# plinkykeeb_choc_12Feb2022.net
KiCad netlist of a schematic drawn in EAGLE
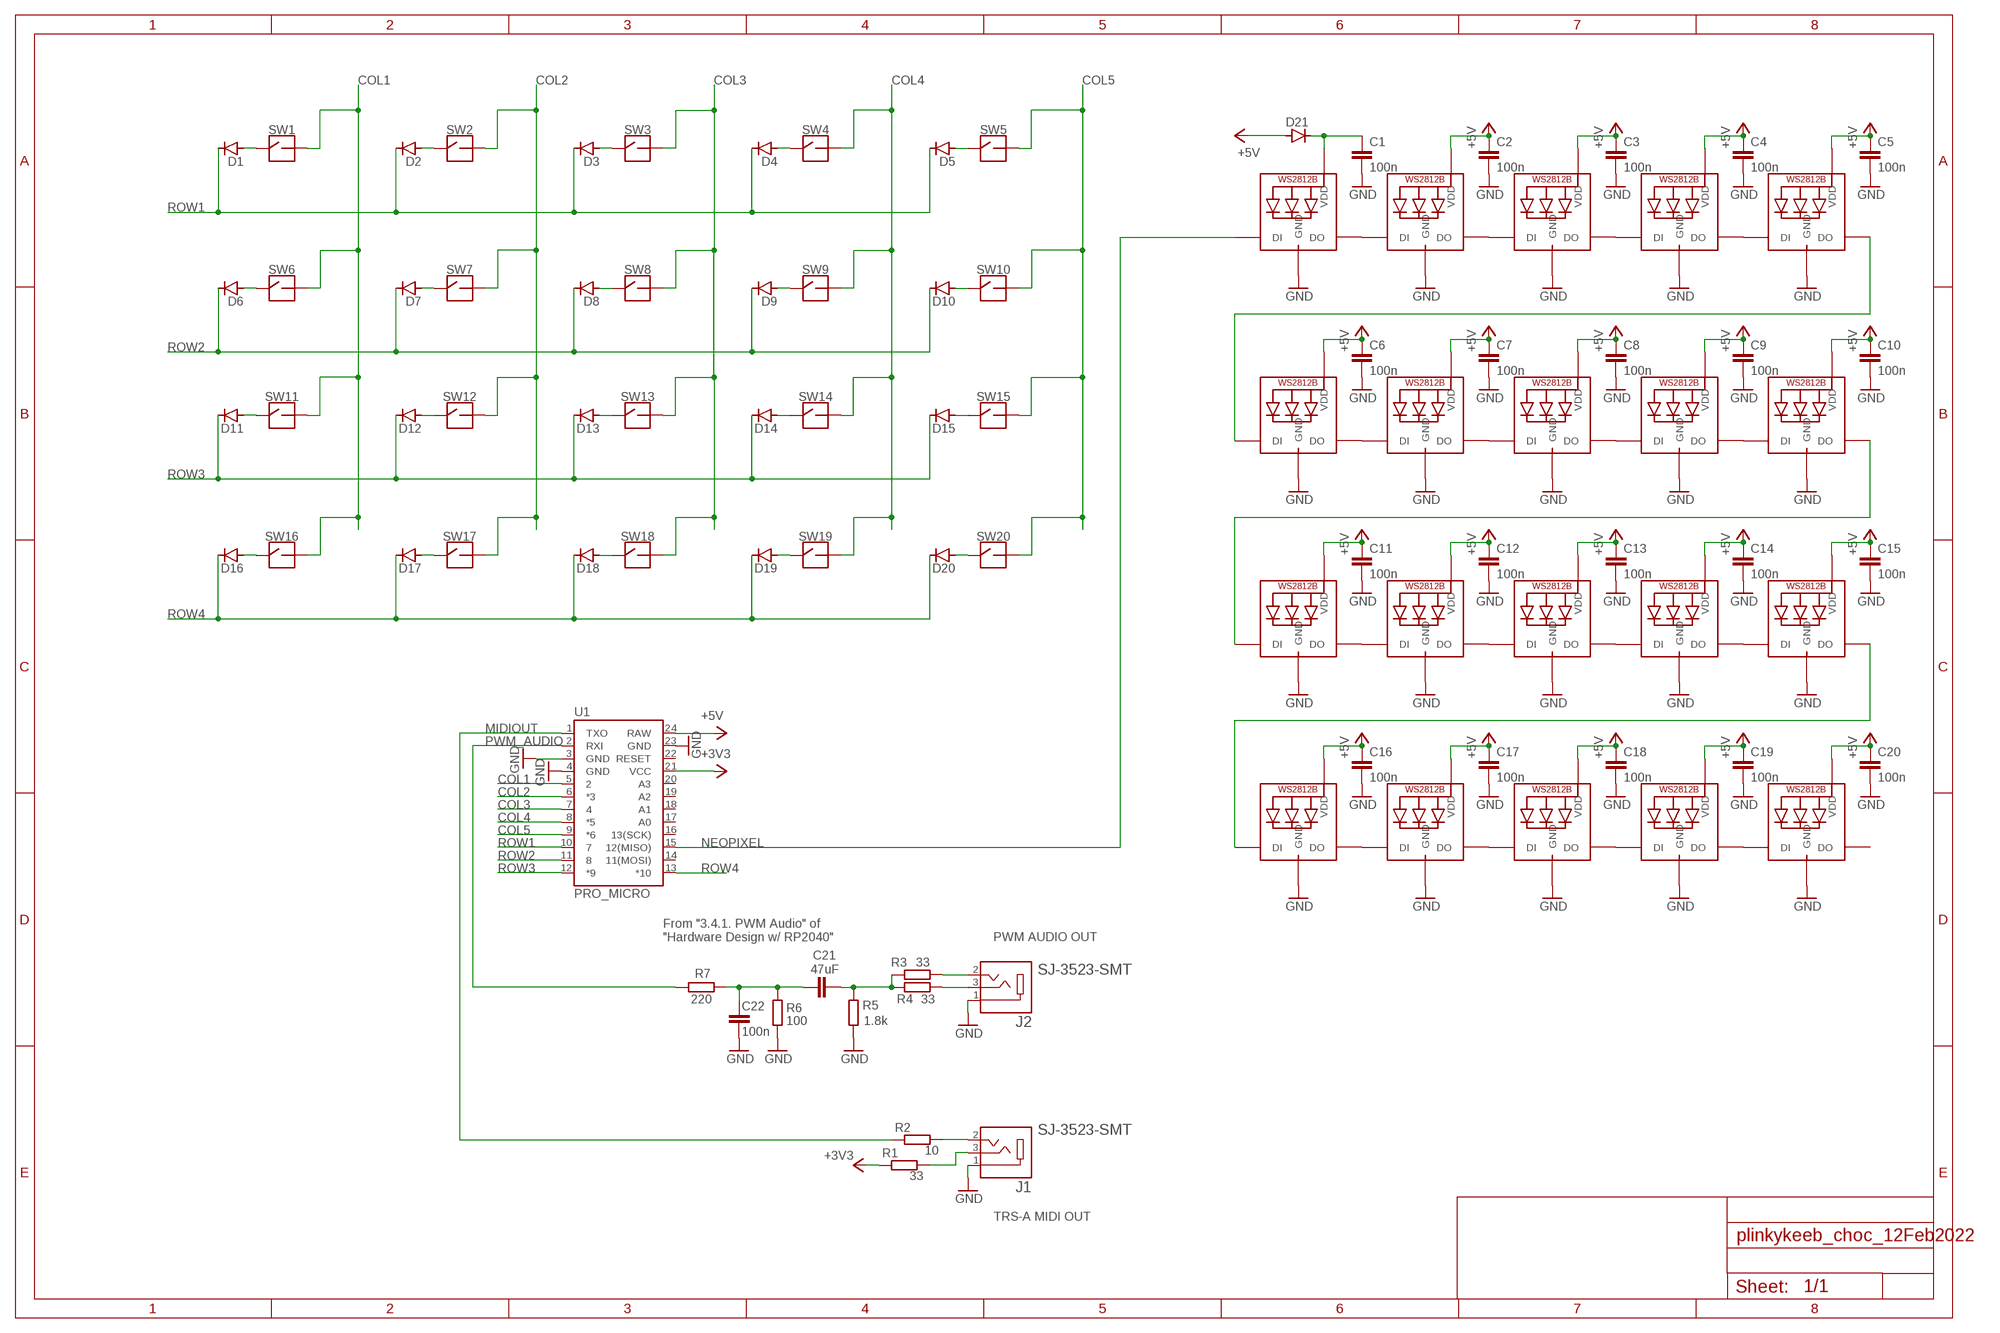
[diagram p0: schematic, sheet 1]

(export (version "E")
  (design (tool "Eeschema 10.0.6"))
  (components
    (comp (ref "C1")
      (value "100n")
      (footprint "eagle-import:C0805")
      (libsource (lib "eagle-import") (part "C-EUC0805"))
    )
    (comp (ref "C2")
      (value "100n")
      (footprint "eagle-import:C0805")
      (libsource (lib "eagle-import") (part "C-EUC0805"))
    )
    (comp (ref "C3")
      (value "100n")
      (footprint "eagle-import:C0805")
      (libsource (lib "eagle-import") (part "C-EUC0805"))
    )
    (comp (ref "C4")
      (value "100n")
      (footprint "eagle-import:C0805")
      (libsource (lib "eagle-import") (part "C-EUC0805"))
    )
    (comp (ref "C5")
      (value "100n")
      (footprint "eagle-import:C0805")
      (libsource (lib "eagle-import") (part "C-EUC0805"))
    )
    (comp (ref "C6")
      (value "100n")
      (footprint "eagle-import:C0805")
      (libsource (lib "eagle-import") (part "C-EUC0805"))
    )
    (comp (ref "C7")
      (value "100n")
      (footprint "eagle-import:C0805")
      (libsource (lib "eagle-import") (part "C-EUC0805"))
    )
    (comp (ref "C8")
      (value "100n")
      (footprint "eagle-import:C0805")
      (libsource (lib "eagle-import") (part "C-EUC0805"))
    )
    (comp (ref "C9")
      (value "100n")
      (footprint "eagle-import:C0805")
      (libsource (lib "eagle-import") (part "C-EUC0805"))
    )
    (comp (ref "C10")
      (value "100n")
      (footprint "eagle-import:C0805")
      (libsource (lib "eagle-import") (part "C-EUC0805"))
    )
    (comp (ref "C11")
      (value "100n")
      (footprint "eagle-import:C0805")
      (libsource (lib "eagle-import") (part "C-EUC0805"))
    )
    (comp (ref "C12")
      (value "100n")
      (footprint "eagle-import:C0805")
      (libsource (lib "eagle-import") (part "C-EUC0805"))
    )
    (comp (ref "C13")
      (value "100n")
      (footprint "eagle-import:C0805")
      (libsource (lib "eagle-import") (part "C-EUC0805"))
    )
    (comp (ref "C14")
      (value "100n")
      (footprint "eagle-import:C0805")
      (libsource (lib "eagle-import") (part "C-EUC0805"))
    )
    (comp (ref "C15")
      (value "100n")
      (footprint "eagle-import:C0805")
      (libsource (lib "eagle-import") (part "C-EUC0805"))
    )
    (comp (ref "C16")
      (value "100n")
      (footprint "eagle-import:C0805")
      (libsource (lib "eagle-import") (part "C-EUC0805"))
    )
    (comp (ref "C17")
      (value "100n")
      (footprint "eagle-import:C0805")
      (libsource (lib "eagle-import") (part "C-EUC0805"))
    )
    (comp (ref "C18")
      (value "100n")
      (footprint "eagle-import:C0805")
      (libsource (lib "eagle-import") (part "C-EUC0805"))
    )
    (comp (ref "C19")
      (value "100n")
      (footprint "eagle-import:C0805")
      (libsource (lib "eagle-import") (part "C-EUC0805"))
    )
    (comp (ref "C20")
      (value "100n")
      (footprint "eagle-import:C0805")
      (libsource (lib "eagle-import") (part "C-EUC0805"))
    )
    (comp (ref "C21")
      (value "47uF")
      (footprint "eagle-import:C0805")
      (libsource (lib "eagle-import") (part "C-EUC0805"))
    )
    (comp (ref "C22")
      (value "100n")
      (footprint "eagle-import:C0805")
      (libsource (lib "eagle-import") (part "C-EUC0805"))
    )
    (comp (ref "D1")
      (value "D-SOD123")
      (footprint "eagle-import:SOD123")
      (libsource (lib "eagle-import") (part "D-SOD123"))
    )
    (comp (ref "D2")
      (value "D-SOD123")
      (footprint "eagle-import:SOD123")
      (libsource (lib "eagle-import") (part "D-SOD123"))
    )
    (comp (ref "D3")
      (value "D-SOD123")
      (footprint "eagle-import:SOD123")
      (libsource (lib "eagle-import") (part "D-SOD123"))
    )
    (comp (ref "D4")
      (value "D-SOD123")
      (footprint "eagle-import:SOD123")
      (libsource (lib "eagle-import") (part "D-SOD123"))
    )
    (comp (ref "D5")
      (value "D-SOD123")
      (footprint "eagle-import:SOD123")
      (libsource (lib "eagle-import") (part "D-SOD123"))
    )
    (comp (ref "D6")
      (value "D-SOD123")
      (footprint "eagle-import:SOD123")
      (libsource (lib "eagle-import") (part "D-SOD123"))
    )
    (comp (ref "D7")
      (value "D-SOD123")
      (footprint "eagle-import:SOD123")
      (libsource (lib "eagle-import") (part "D-SOD123"))
    )
    (comp (ref "D8")
      (value "D-SOD123")
      (footprint "eagle-import:SOD123")
      (libsource (lib "eagle-import") (part "D-SOD123"))
    )
    (comp (ref "D9")
      (value "D-SOD123")
      (footprint "eagle-import:SOD123")
      (libsource (lib "eagle-import") (part "D-SOD123"))
    )
    (comp (ref "D10")
      (value "D-SOD123")
      (footprint "eagle-import:SOD123")
      (libsource (lib "eagle-import") (part "D-SOD123"))
    )
    (comp (ref "D11")
      (value "D-SOD123")
      (footprint "eagle-import:SOD123")
      (libsource (lib "eagle-import") (part "D-SOD123"))
    )
    (comp (ref "D12")
      (value "D-SOD123")
      (footprint "eagle-import:SOD123")
      (libsource (lib "eagle-import") (part "D-SOD123"))
    )
    (comp (ref "D13")
      (value "D-SOD123")
      (footprint "eagle-import:SOD123")
      (libsource (lib "eagle-import") (part "D-SOD123"))
    )
    (comp (ref "D14")
      (value "D-SOD123")
      (footprint "eagle-import:SOD123")
      (libsource (lib "eagle-import") (part "D-SOD123"))
    )
    (comp (ref "D15")
      (value "D-SOD123")
      (footprint "eagle-import:SOD123")
      (libsource (lib "eagle-import") (part "D-SOD123"))
    )
    (comp (ref "D16")
      (value "D-SOD123")
      (footprint "eagle-import:SOD123")
      (libsource (lib "eagle-import") (part "D-SOD123"))
    )
    (comp (ref "D17")
      (value "D-SOD123")
      (footprint "eagle-import:SOD123")
      (libsource (lib "eagle-import") (part "D-SOD123"))
    )
    (comp (ref "D18")
      (value "D-SOD123")
      (footprint "eagle-import:SOD123")
      (libsource (lib "eagle-import") (part "D-SOD123"))
    )
    (comp (ref "D19")
      (value "D-SOD123")
      (footprint "eagle-import:SOD123")
      (libsource (lib "eagle-import") (part "D-SOD123"))
    )
    (comp (ref "D20")
      (value "D-SOD123")
      (footprint "eagle-import:SOD123")
      (libsource (lib "eagle-import") (part "D-SOD123"))
    )
    (comp (ref "D21")
      (value "D-SOD123")
      (footprint "eagle-import:SOD123")
      (libsource (lib "eagle-import") (part "D-SOD123"))
    )
    (comp (ref "J1")
      (value "SJ-3523-SMT")
      (footprint "eagle-import:CUI_SJ-3523-SMT")
      (fields
        (field (name "DIGI-KEY_PART_NUMBER") "CP-3523SJCT-ND")
        (field (name "MF") "CUI Devices")
        (field (name "MP") "SJ-3523-SMT-TR")
      )
      (libsource (lib "eagle-import") (part "SJ-3523-SMT"))
    )
    (comp (ref "J2")
      (value "SJ-3523-SMT")
      (footprint "eagle-import:CUI_SJ-3523-SMT")
      (fields
        (field (name "DIGI-KEY_PART_NUMBER") "CP-3523SJCT-ND")
        (field (name "MF") "CUI Devices")
        (field (name "MP") "SJ-3523-SMT-TR")
      )
      (libsource (lib "eagle-import") (part "SJ-3523-SMT"))
    )
    (comp (ref "LED1")
      (value "MICROBUILDER_WS2812B_SK6812E")
      (footprint "eagle-import:MICROBUILDER_NEO3535_REVERSE")
      (libsource (lib "eagle-import") (part "MICROBUILDER_WS2812B_SK6812E"))
    )
    (comp (ref "LED2")
      (value "MICROBUILDER_WS2812B_SK6812E")
      (footprint "eagle-import:MICROBUILDER_NEO3535_REVERSE")
      (libsource (lib "eagle-import") (part "MICROBUILDER_WS2812B_SK6812E"))
    )
    (comp (ref "LED3")
      (value "MICROBUILDER_WS2812B_SK6812E")
      (footprint "eagle-import:MICROBUILDER_NEO3535_REVERSE")
      (libsource (lib "eagle-import") (part "MICROBUILDER_WS2812B_SK6812E"))
    )
    (comp (ref "LED4")
      (value "MICROBUILDER_WS2812B_SK6812E")
      (footprint "eagle-import:MICROBUILDER_NEO3535_REVERSE")
      (libsource (lib "eagle-import") (part "MICROBUILDER_WS2812B_SK6812E"))
    )
    (comp (ref "LED5")
      (value "MICROBUILDER_WS2812B_SK6812E")
      (footprint "eagle-import:MICROBUILDER_NEO3535_REVERSE")
      (libsource (lib "eagle-import") (part "MICROBUILDER_WS2812B_SK6812E"))
    )
    (comp (ref "LED6")
      (value "MICROBUILDER_WS2812B_SK6812E")
      (footprint "eagle-import:MICROBUILDER_NEO3535_REVERSE")
      (libsource (lib "eagle-import") (part "MICROBUILDER_WS2812B_SK6812E"))
    )
    (comp (ref "LED7")
      (value "MICROBUILDER_WS2812B_SK6812E")
      (footprint "eagle-import:MICROBUILDER_NEO3535_REVERSE")
      (libsource (lib "eagle-import") (part "MICROBUILDER_WS2812B_SK6812E"))
    )
    (comp (ref "LED8")
      (value "MICROBUILDER_WS2812B_SK6812E")
      (footprint "eagle-import:MICROBUILDER_NEO3535_REVERSE")
      (libsource (lib "eagle-import") (part "MICROBUILDER_WS2812B_SK6812E"))
    )
    (comp (ref "LED9")
      (value "MICROBUILDER_WS2812B_SK6812E")
      (footprint "eagle-import:MICROBUILDER_NEO3535_REVERSE")
      (libsource (lib "eagle-import") (part "MICROBUILDER_WS2812B_SK6812E"))
    )
    (comp (ref "LED10")
      (value "MICROBUILDER_WS2812B_SK6812E")
      (footprint "eagle-import:MICROBUILDER_NEO3535_REVERSE")
      (libsource (lib "eagle-import") (part "MICROBUILDER_WS2812B_SK6812E"))
    )
    (comp (ref "LED11")
      (value "MICROBUILDER_WS2812B_SK6812E")
      (footprint "eagle-import:MICROBUILDER_NEO3535_REVERSE")
      (libsource (lib "eagle-import") (part "MICROBUILDER_WS2812B_SK6812E"))
    )
    (comp (ref "LED12")
      (value "MICROBUILDER_WS2812B_SK6812E")
      (footprint "eagle-import:MICROBUILDER_NEO3535_REVERSE")
      (libsource (lib "eagle-import") (part "MICROBUILDER_WS2812B_SK6812E"))
    )
    (comp (ref "LED13")
      (value "MICROBUILDER_WS2812B_SK6812E")
      (footprint "eagle-import:MICROBUILDER_NEO3535_REVERSE")
      (libsource (lib "eagle-import") (part "MICROBUILDER_WS2812B_SK6812E"))
    )
    (comp (ref "LED14")
      (value "MICROBUILDER_WS2812B_SK6812E")
      (footprint "eagle-import:MICROBUILDER_NEO3535_REVERSE")
      (libsource (lib "eagle-import") (part "MICROBUILDER_WS2812B_SK6812E"))
    )
    (comp (ref "LED15")
      (value "MICROBUILDER_WS2812B_SK6812E")
      (footprint "eagle-import:MICROBUILDER_NEO3535_REVERSE")
      (libsource (lib "eagle-import") (part "MICROBUILDER_WS2812B_SK6812E"))
    )
    (comp (ref "LED16")
      (value "MICROBUILDER_WS2812B_SK6812E")
      (footprint "eagle-import:MICROBUILDER_NEO3535_REVERSE")
      (libsource (lib "eagle-import") (part "MICROBUILDER_WS2812B_SK6812E"))
    )
    (comp (ref "LED17")
      (value "MICROBUILDER_WS2812B_SK6812E")
      (footprint "eagle-import:MICROBUILDER_NEO3535_REVERSE")
      (libsource (lib "eagle-import") (part "MICROBUILDER_WS2812B_SK6812E"))
    )
    (comp (ref "LED18")
      (value "MICROBUILDER_WS2812B_SK6812E")
      (footprint "eagle-import:MICROBUILDER_NEO3535_REVERSE")
      (libsource (lib "eagle-import") (part "MICROBUILDER_WS2812B_SK6812E"))
    )
    (comp (ref "LED19")
      (value "MICROBUILDER_WS2812B_SK6812E")
      (footprint "eagle-import:MICROBUILDER_NEO3535_REVERSE")
      (libsource (lib "eagle-import") (part "MICROBUILDER_WS2812B_SK6812E"))
    )
    (comp (ref "LED20")
      (value "MICROBUILDER_WS2812B_SK6812E")
      (footprint "eagle-import:MICROBUILDER_NEO3535_REVERSE")
      (libsource (lib "eagle-import") (part "MICROBUILDER_WS2812B_SK6812E"))
    )
    (comp (ref "R1")
      (value "33")
      (footprint "eagle-import:R0805")
      (libsource (lib "eagle-import") (part "R-EU_R0805"))
    )
    (comp (ref "R2")
      (value "10")
      (footprint "eagle-import:R0805")
      (libsource (lib "eagle-import") (part "R-EU_R0805"))
    )
    (comp (ref "R3")
      (value "33")
      (footprint "eagle-import:R0805")
      (libsource (lib "eagle-import") (part "R-EU_R0805"))
    )
    (comp (ref "R4")
      (value "33")
      (footprint "eagle-import:R0805")
      (libsource (lib "eagle-import") (part "R-EU_R0805"))
    )
    (comp (ref "R5")
      (value "1.8k")
      (footprint "eagle-import:R0805")
      (libsource (lib "eagle-import") (part "R-EU_R0805"))
    )
    (comp (ref "R6")
      (value "100")
      (footprint "eagle-import:R0805")
      (libsource (lib "eagle-import") (part "R-EU_R0805"))
    )
    (comp (ref "R7")
      (value "220")
      (footprint "eagle-import:R0805")
      (libsource (lib "eagle-import") (part "R-EU_R0805"))
    )
    (comp (ref "SW1")
      (value "KBD_SWITCHKALIH_CHOC_SOCKET")
      (footprint "eagle-import:KALIH_SOCKET_CHOC")
      (libsource (lib "eagle-import") (part "KBD_SWITCHKALIH_CHOC_SOCKET"))
    )
    (comp (ref "SW2")
      (value "KBD_SWITCHKALIH_CHOC_SOCKET")
      (footprint "eagle-import:KALIH_SOCKET_CHOC")
      (libsource (lib "eagle-import") (part "KBD_SWITCHKALIH_CHOC_SOCKET"))
    )
    (comp (ref "SW3")
      (value "KBD_SWITCHKALIH_CHOC_SOCKET")
      (footprint "eagle-import:KALIH_SOCKET_CHOC")
      (libsource (lib "eagle-import") (part "KBD_SWITCHKALIH_CHOC_SOCKET"))
    )
    (comp (ref "SW4")
      (value "KBD_SWITCHKALIH_CHOC_SOCKET")
      (footprint "eagle-import:KALIH_SOCKET_CHOC")
      (libsource (lib "eagle-import") (part "KBD_SWITCHKALIH_CHOC_SOCKET"))
    )
    (comp (ref "SW5")
      (value "KBD_SWITCHKALIH_CHOC_SOCKET")
      (footprint "eagle-import:KALIH_SOCKET_CHOC")
      (libsource (lib "eagle-import") (part "KBD_SWITCHKALIH_CHOC_SOCKET"))
    )
    (comp (ref "SW6")
      (value "KBD_SWITCHKALIH_CHOC_SOCKET")
      (footprint "eagle-import:KALIH_SOCKET_CHOC")
      (libsource (lib "eagle-import") (part "KBD_SWITCHKALIH_CHOC_SOCKET"))
    )
    (comp (ref "SW7")
      (value "KBD_SWITCHKALIH_CHOC_SOCKET")
      (footprint "eagle-import:KALIH_SOCKET_CHOC")
      (libsource (lib "eagle-import") (part "KBD_SWITCHKALIH_CHOC_SOCKET"))
    )
    (comp (ref "SW8")
      (value "KBD_SWITCHKALIH_CHOC_SOCKET")
      (footprint "eagle-import:KALIH_SOCKET_CHOC")
      (libsource (lib "eagle-import") (part "KBD_SWITCHKALIH_CHOC_SOCKET"))
    )
    (comp (ref "SW9")
      (value "KBD_SWITCHKALIH_CHOC_SOCKET")
      (footprint "eagle-import:KALIH_SOCKET_CHOC")
      (libsource (lib "eagle-import") (part "KBD_SWITCHKALIH_CHOC_SOCKET"))
    )
    (comp (ref "SW10")
      (value "KBD_SWITCHKALIH_CHOC_SOCKET")
      (footprint "eagle-import:KALIH_SOCKET_CHOC")
      (libsource (lib "eagle-import") (part "KBD_SWITCHKALIH_CHOC_SOCKET"))
    )
    (comp (ref "SW11")
      (value "KBD_SWITCHKALIH_CHOC_SOCKET")
      (footprint "eagle-import:KALIH_SOCKET_CHOC")
      (libsource (lib "eagle-import") (part "KBD_SWITCHKALIH_CHOC_SOCKET"))
    )
    (comp (ref "SW12")
      (value "KBD_SWITCHKALIH_CHOC_SOCKET")
      (footprint "eagle-import:KALIH_SOCKET_CHOC")
      (libsource (lib "eagle-import") (part "KBD_SWITCHKALIH_CHOC_SOCKET"))
    )
    (comp (ref "SW13")
      (value "KBD_SWITCHKALIH_CHOC_SOCKET")
      (footprint "eagle-import:KALIH_SOCKET_CHOC")
      (libsource (lib "eagle-import") (part "KBD_SWITCHKALIH_CHOC_SOCKET"))
    )
    (comp (ref "SW14")
      (value "KBD_SWITCHKALIH_CHOC_SOCKET")
      (footprint "eagle-import:KALIH_SOCKET_CHOC")
      (libsource (lib "eagle-import") (part "KBD_SWITCHKALIH_CHOC_SOCKET"))
    )
    (comp (ref "SW15")
      (value "KBD_SWITCHKALIH_CHOC_SOCKET")
      (footprint "eagle-import:KALIH_SOCKET_CHOC")
      (libsource (lib "eagle-import") (part "KBD_SWITCHKALIH_CHOC_SOCKET"))
    )
    (comp (ref "SW16")
      (value "KBD_SWITCHKALIH_CHOC_SOCKET")
      (footprint "eagle-import:KALIH_SOCKET_CHOC")
      (libsource (lib "eagle-import") (part "KBD_SWITCHKALIH_CHOC_SOCKET"))
    )
    (comp (ref "SW17")
      (value "KBD_SWITCHKALIH_CHOC_SOCKET")
      (footprint "eagle-import:KALIH_SOCKET_CHOC")
      (libsource (lib "eagle-import") (part "KBD_SWITCHKALIH_CHOC_SOCKET"))
    )
    (comp (ref "SW18")
      (value "KBD_SWITCHKALIH_CHOC_SOCKET")
      (footprint "eagle-import:KALIH_SOCKET_CHOC")
      (libsource (lib "eagle-import") (part "KBD_SWITCHKALIH_CHOC_SOCKET"))
    )
    (comp (ref "SW19")
      (value "KBD_SWITCHKALIH_CHOC_SOCKET")
      (footprint "eagle-import:KALIH_SOCKET_CHOC")
      (libsource (lib "eagle-import") (part "KBD_SWITCHKALIH_CHOC_SOCKET"))
    )
    (comp (ref "SW20")
      (value "KBD_SWITCHKALIH_CHOC_SOCKET")
      (footprint "eagle-import:KALIH_SOCKET_CHOC")
      (libsource (lib "eagle-import") (part "KBD_SWITCHKALIH_CHOC_SOCKET"))
    )
    (comp (ref "U1")
      (value "PRO_MICRO")
      (footprint "eagle-import:SPARKFUN_PRO_MICRO")
      (libsource (lib "eagle-import") (part "SPARKFUN_PRO_MICRO"))
    )
  )
  (nets
    (net (code "1") (name "+3V3") (class "Default")
      (node (ref "R1") (pin "2") (pinfunction "2_2") (pintype "passive"))
      (node (ref "U1") (pin "21") (pinfunction "VCC_21") (pintype "power_in"))
    )
    (net (code "2") (name "+5V") (class "Default")
      (node (ref "C10") (pin "1") (pinfunction "1_1") (pintype "passive"))
      (node (ref "C11") (pin "1") (pinfunction "1_1") (pintype "passive"))
      (node (ref "C12") (pin "1") (pinfunction "1_1") (pintype "passive"))
      (node (ref "C13") (pin "1") (pinfunction "1_1") (pintype "passive"))
      (node (ref "C14") (pin "1") (pinfunction "1_1") (pintype "passive"))
      (node (ref "C15") (pin "1") (pinfunction "1_1") (pintype "passive"))
      (node (ref "C16") (pin "1") (pinfunction "1_1") (pintype "passive"))
      (node (ref "C17") (pin "1") (pinfunction "1_1") (pintype "passive"))
      (node (ref "C18") (pin "1") (pinfunction "1_1") (pintype "passive"))
      (node (ref "C19") (pin "1") (pinfunction "1_1") (pintype "passive"))
      (node (ref "C2") (pin "1") (pinfunction "1_1") (pintype "passive"))
      (node (ref "C20") (pin "1") (pinfunction "1_1") (pintype "passive"))
      (node (ref "C3") (pin "1") (pinfunction "1_1") (pintype "passive"))
      (node (ref "C4") (pin "1") (pinfunction "1_1") (pintype "passive"))
      (node (ref "C5") (pin "1") (pinfunction "1_1") (pintype "passive"))
      (node (ref "C6") (pin "1") (pinfunction "1_1") (pintype "passive"))
      (node (ref "C7") (pin "1") (pinfunction "1_1") (pintype "passive"))
      (node (ref "C8") (pin "1") (pinfunction "1_1") (pintype "passive"))
      (node (ref "C9") (pin "1") (pinfunction "1_1") (pintype "passive"))
      (node (ref "D21") (pin "2") (pinfunction "A_2") (pintype "passive"))
      (node (ref "LED10") (pin "1-VDD") (pinfunction "VDD_1-VDD") (pintype "power_in"))
      (node (ref "LED11") (pin "1-VDD") (pinfunction "VDD_1-VDD") (pintype "power_in"))
      (node (ref "LED12") (pin "1-VDD") (pinfunction "VDD_1-VDD") (pintype "power_in"))
      (node (ref "LED13") (pin "1-VDD") (pinfunction "VDD_1-VDD") (pintype "power_in"))
      (node (ref "LED14") (pin "1-VDD") (pinfunction "VDD_1-VDD") (pintype "power_in"))
      (node (ref "LED15") (pin "1-VDD") (pinfunction "VDD_1-VDD") (pintype "power_in"))
      (node (ref "LED16") (pin "1-VDD") (pinfunction "VDD_1-VDD") (pintype "power_in"))
      (node (ref "LED17") (pin "1-VDD") (pinfunction "VDD_1-VDD") (pintype "power_in"))
      (node (ref "LED18") (pin "1-VDD") (pinfunction "VDD_1-VDD") (pintype "power_in"))
      (node (ref "LED19") (pin "1-VDD") (pinfunction "VDD_1-VDD") (pintype "power_in"))
      (node (ref "LED2") (pin "1-VDD") (pinfunction "VDD_1-VDD") (pintype "power_in"))
      (node (ref "LED20") (pin "1-VDD") (pinfunction "VDD_1-VDD") (pintype "power_in"))
      (node (ref "LED3") (pin "1-VDD") (pinfunction "VDD_1-VDD") (pintype "power_in"))
      (node (ref "LED4") (pin "1-VDD") (pinfunction "VDD_1-VDD") (pintype "power_in"))
      (node (ref "LED5") (pin "1-VDD") (pinfunction "VDD_1-VDD") (pintype "power_in"))
      (node (ref "LED6") (pin "1-VDD") (pinfunction "VDD_1-VDD") (pintype "power_in"))
      (node (ref "LED7") (pin "1-VDD") (pinfunction "VDD_1-VDD") (pintype "power_in"))
      (node (ref "LED8") (pin "1-VDD") (pinfunction "VDD_1-VDD") (pintype "power_in"))
      (node (ref "LED9") (pin "1-VDD") (pinfunction "VDD_1-VDD") (pintype "power_in"))
      (node (ref "U1") (pin "24") (pinfunction "RAW_24") (pintype "power_in"))
    )
    (net (code "3") (name "/COL1") (class "Default")
      (node (ref "SW1") (pin "2") (pinfunction "2_2") (pintype "passive"))
      (node (ref "SW11") (pin "2") (pinfunction "2_2") (pintype "passive"))
      (node (ref "SW16") (pin "2") (pinfunction "2_2") (pintype "passive"))
      (node (ref "SW6") (pin "2") (pinfunction "2_2") (pintype "passive"))
      (node (ref "U1") (pin "5") (pinfunction "2_5") (pintype "bidirectional"))
    )
    (net (code "4") (name "/COL2") (class "Default")
      (node (ref "SW12") (pin "2") (pinfunction "2_2") (pintype "passive"))
      (node (ref "SW17") (pin "2") (pinfunction "2_2") (pintype "passive"))
      (node (ref "SW2") (pin "2") (pinfunction "2_2") (pintype "passive"))
      (node (ref "SW7") (pin "2") (pinfunction "2_2") (pintype "passive"))
      (node (ref "U1") (pin "6") (pinfunction "*3_6") (pintype "bidirectional"))
    )
    (net (code "5") (name "/COL3") (class "Default")
      (node (ref "SW13") (pin "2") (pinfunction "2_2") (pintype "passive"))
      (node (ref "SW18") (pin "2") (pinfunction "2_2") (pintype "passive"))
      (node (ref "SW3") (pin "2") (pinfunction "2_2") (pintype "passive"))
      (node (ref "SW8") (pin "2") (pinfunction "2_2") (pintype "passive"))
      (node (ref "U1") (pin "7") (pinfunction "4_7") (pintype "bidirectional"))
    )
    (net (code "6") (name "/COL4") (class "Default")
      (node (ref "SW14") (pin "2") (pinfunction "2_2") (pintype "passive"))
      (node (ref "SW19") (pin "2") (pinfunction "2_2") (pintype "passive"))
      (node (ref "SW4") (pin "2") (pinfunction "2_2") (pintype "passive"))
      (node (ref "SW9") (pin "2") (pinfunction "2_2") (pintype "passive"))
      (node (ref "U1") (pin "8") (pinfunction "*5_8") (pintype "bidirectional"))
    )
    (net (code "7") (name "/COL5") (class "Default")
      (node (ref "SW10") (pin "2") (pinfunction "2_2") (pintype "passive"))
      (node (ref "SW15") (pin "2") (pinfunction "2_2") (pintype "passive"))
      (node (ref "SW20") (pin "2") (pinfunction "2_2") (pintype "passive"))
      (node (ref "SW5") (pin "2") (pinfunction "2_2") (pintype "passive"))
      (node (ref "U1") (pin "9") (pinfunction "*6_9") (pintype "bidirectional"))
    )
    (net (code "8") (name "/MIDIOUT") (class "Default")
      (node (ref "R2") (pin "2") (pinfunction "2_2") (pintype "passive"))
      (node (ref "U1") (pin "1") (pinfunction "TXO_1") (pintype "bidirectional"))
    )
    (net (code "9") (name "/NEOPIXEL") (class "Default")
      (node (ref "LED1") (pin "4-DIN") (pinfunction "DI_4-DIN") (pintype "input"))
      (node (ref "U1") (pin "15") (pinfunction "12(MISO)_15") (pintype "bidirectional"))
    )
    (net (code "10") (name "/PWM_AUDIO") (class "Default")
      (node (ref "R7") (pin "2") (pinfunction "2_2") (pintype "passive"))
      (node (ref "U1") (pin "2") (pinfunction "RXI_2") (pintype "bidirectional"))
    )
    (net (code "11") (name "/ROW1") (class "Default")
      (node (ref "D1") (pin "1") (pinfunction "C_1") (pintype "passive"))
      (node (ref "D2") (pin "1") (pinfunction "C_1") (pintype "passive"))
      (node (ref "D3") (pin "1") (pinfunction "C_1") (pintype "passive"))
      (node (ref "D4") (pin "1") (pinfunction "C_1") (pintype "passive"))
      (node (ref "D5") (pin "1") (pinfunction "C_1") (pintype "passive"))
      (node (ref "U1") (pin "10") (pinfunction "7_10") (pintype "bidirectional"))
    )
    (net (code "12") (name "/ROW2") (class "Default")
      (node (ref "D10") (pin "1") (pinfunction "C_1") (pintype "passive"))
      (node (ref "D6") (pin "1") (pinfunction "C_1") (pintype "passive"))
      (node (ref "D7") (pin "1") (pinfunction "C_1") (pintype "passive"))
      (node (ref "D8") (pin "1") (pinfunction "C_1") (pintype "passive"))
      (node (ref "D9") (pin "1") (pinfunction "C_1") (pintype "passive"))
      (node (ref "U1") (pin "11") (pinfunction "8_11") (pintype "bidirectional"))
    )
    (net (code "13") (name "/ROW3") (class "Default")
      (node (ref "D11") (pin "1") (pinfunction "C_1") (pintype "passive"))
      (node (ref "D12") (pin "1") (pinfunction "C_1") (pintype "passive"))
      (node (ref "D13") (pin "1") (pinfunction "C_1") (pintype "passive"))
      (node (ref "D14") (pin "1") (pinfunction "C_1") (pintype "passive"))
      (node (ref "D15") (pin "1") (pinfunction "C_1") (pintype "passive"))
      (node (ref "U1") (pin "12") (pinfunction "*9_12") (pintype "bidirectional"))
    )
    (net (code "14") (name "/ROW4") (class "Default")
      (node (ref "D16") (pin "1") (pinfunction "C_1") (pintype "passive"))
      (node (ref "D17") (pin "1") (pinfunction "C_1") (pintype "passive"))
      (node (ref "D18") (pin "1") (pinfunction "C_1") (pintype "passive"))
      (node (ref "D19") (pin "1") (pinfunction "C_1") (pintype "passive"))
      (node (ref "D20") (pin "1") (pinfunction "C_1") (pintype "passive"))
      (node (ref "U1") (pin "13") (pinfunction "*10_13") (pintype "bidirectional"))
    )
    (net (code "15") (name "GND") (class "Default")
      (node (ref "C1") (pin "2") (pinfunction "2_2") (pintype "passive"))
      (node (ref "C10") (pin "2") (pinfunction "2_2") (pintype "passive"))
      (node (ref "C11") (pin "2") (pinfunction "2_2") (pintype "passive"))
      (node (ref "C12") (pin "2") (pinfunction "2_2") (pintype "passive"))
      (node (ref "C13") (pin "2") (pinfunction "2_2") (pintype "passive"))
      (node (ref "C14") (pin "2") (pinfunction "2_2") (pintype "passive"))
      (node (ref "C15") (pin "2") (pinfunction "2_2") (pintype "passive"))
      (node (ref "C16") (pin "2") (pinfunction "2_2") (pintype "passive"))
      (node (ref "C17") (pin "2") (pinfunction "2_2") (pintype "passive"))
      (node (ref "C18") (pin "2") (pinfunction "2_2") (pintype "passive"))
      (node (ref "C19") (pin "2") (pinfunction "2_2") (pintype "passive"))
      (node (ref "C2") (pin "2") (pinfunction "2_2") (pintype "passive"))
      (node (ref "C20") (pin "2") (pinfunction "2_2") (pintype "passive"))
      (node (ref "C22") (pin "2") (pinfunction "2_2") (pintype "passive"))
      (node (ref "C3") (pin "2") (pinfunction "2_2") (pintype "passive"))
      (node (ref "C4") (pin "2") (pinfunction "2_2") (pintype "passive"))
      (node (ref "C5") (pin "2") (pinfunction "2_2") (pintype "passive"))
      (node (ref "C6") (pin "2") (pinfunction "2_2") (pintype "passive"))
      (node (ref "C7") (pin "2") (pinfunction "2_2") (pintype "passive"))
      (node (ref "C8") (pin "2") (pinfunction "2_2") (pintype "passive"))
      (node (ref "C9") (pin "2") (pinfunction "2_2") (pintype "passive"))
      (node (ref "J1") (pin "1") (pinfunction "1_1") (pintype "passive"))
      (node (ref "J2") (pin "1") (pinfunction "1_1") (pintype "passive"))
      (node (ref "LED1") (pin "3-GND") (pinfunction "GND_3-GND") (pintype "power_in"))
      (node (ref "LED10") (pin "3-GND") (pinfunction "GND_3-GND") (pintype "power_in"))
      (node (ref "LED11") (pin "3-GND") (pinfunction "GND_3-GND") (pintype "power_in"))
      (node (ref "LED12") (pin "3-GND") (pinfunction "GND_3-GND") (pintype "power_in"))
      (node (ref "LED13") (pin "3-GND") (pinfunction "GND_3-GND") (pintype "power_in"))
      (node (ref "LED14") (pin "3-GND") (pinfunction "GND_3-GND") (pintype "power_in"))
      (node (ref "LED15") (pin "3-GND") (pinfunction "GND_3-GND") (pintype "power_in"))
      (node (ref "LED16") (pin "3-GND") (pinfunction "GND_3-GND") (pintype "power_in"))
      (node (ref "LED17") (pin "3-GND") (pinfunction "GND_3-GND") (pintype "power_in"))
      (node (ref "LED18") (pin "3-GND") (pinfunction "GND_3-GND") (pintype "power_in"))
      (node (ref "LED19") (pin "3-GND") (pinfunction "GND_3-GND") (pintype "power_in"))
      (node (ref "LED2") (pin "3-GND") (pinfunction "GND_3-GND") (pintype "power_in"))
      (node (ref "LED20") (pin "3-GND") (pinfunction "GND_3-GND") (pintype "power_in"))
      (node (ref "LED3") (pin "3-GND") (pinfunction "GND_3-GND") (pintype "power_in"))
      (node (ref "LED4") (pin "3-GND") (pinfunction "GND_3-GND") (pintype "power_in"))
      (node (ref "LED5") (pin "3-GND") (pinfunction "GND_3-GND") (pintype "power_in"))
      (node (ref "LED6") (pin "3-GND") (pinfunction "GND_3-GND") (pintype "power_in"))
      (node (ref "LED7") (pin "3-GND") (pinfunction "GND_3-GND") (pintype "power_in"))
      (node (ref "LED8") (pin "3-GND") (pinfunction "GND_3-GND") (pintype "power_in"))
      (node (ref "LED9") (pin "3-GND") (pinfunction "GND_3-GND") (pintype "power_in"))
      (node (ref "R5") (pin "2") (pinfunction "2_2") (pintype "passive"))
      (node (ref "R6") (pin "1") (pinfunction "1_1") (pintype "passive"))
      (node (ref "U1") (pin "23") (pinfunction "GND_23") (pintype "power_in"))
      (node (ref "U1") (pin "3") (pinfunction "GND_3") (pintype "power_in"))
      (node (ref "U1") (pin "4") (pinfunction "GND_4") (pintype "power_in"))
    )
    (net (code "16") (name "Net-(C21-Pad1)") (class "Default")
      (node (ref "C21") (pin "1") (pinfunction "1_1") (pintype "passive"))
      (node (ref "C22") (pin "1") (pinfunction "1_1") (pintype "passive"))
      (node (ref "R6") (pin "2") (pinfunction "2_2") (pintype "passive"))
      (node (ref "R7") (pin "1") (pinfunction "1_1") (pintype "passive"))
    )
    (net (code "17") (name "Net-(C21-Pad2)") (class "Default")
      (node (ref "C21") (pin "2") (pinfunction "2_2") (pintype "passive"))
      (node (ref "R3") (pin "2") (pinfunction "2_2") (pintype "passive"))
      (node (ref "R4") (pin "2") (pinfunction "2_2") (pintype "passive"))
      (node (ref "R5") (pin "1") (pinfunction "1_1") (pintype "passive"))
    )
    (net (code "18") (name "Net-(D1-A)") (class "Default")
      (node (ref "D1") (pin "2") (pinfunction "A_2") (pintype "passive"))
      (node (ref "SW1") (pin "1") (pinfunction "1_1") (pintype "passive"))
    )
    (net (code "19") (name "Net-(D2-A)") (class "Default")
      (node (ref "D2") (pin "2") (pinfunction "A_2") (pintype "passive"))
      (node (ref "SW2") (pin "1") (pinfunction "1_1") (pintype "passive"))
    )
    (net (code "20") (name "Net-(D3-A)") (class "Default")
      (node (ref "D3") (pin "2") (pinfunction "A_2") (pintype "passive"))
      (node (ref "SW3") (pin "1") (pinfunction "1_1") (pintype "passive"))
    )
    (net (code "21") (name "Net-(D4-A)") (class "Default")
      (node (ref "D4") (pin "2") (pinfunction "A_2") (pintype "passive"))
      (node (ref "SW4") (pin "1") (pinfunction "1_1") (pintype "passive"))
    )
    (net (code "22") (name "Net-(D5-A)") (class "Default")
      (node (ref "D5") (pin "2") (pinfunction "A_2") (pintype "passive"))
      (node (ref "SW5") (pin "1") (pinfunction "1_1") (pintype "passive"))
    )
    (net (code "23") (name "Net-(D6-A)") (class "Default")
      (node (ref "D6") (pin "2") (pinfunction "A_2") (pintype "passive"))
      (node (ref "SW6") (pin "1") (pinfunction "1_1") (pintype "passive"))
    )
    (net (code "24") (name "Net-(D7-A)") (class "Default")
      (node (ref "D7") (pin "2") (pinfunction "A_2") (pintype "passive"))
      (node (ref "SW7") (pin "1") (pinfunction "1_1") (pintype "passive"))
    )
    (net (code "25") (name "Net-(D8-A)") (class "Default")
      (node (ref "D8") (pin "2") (pinfunction "A_2") (pintype "passive"))
      (node (ref "SW8") (pin "1") (pinfunction "1_1") (pintype "passive"))
    )
    (net (code "26") (name "Net-(D9-A)") (class "Default")
      (node (ref "D9") (pin "2") (pinfunction "A_2") (pintype "passive"))
      (node (ref "SW9") (pin "1") (pinfunction "1_1") (pintype "passive"))
    )
    (net (code "27") (name "Net-(D10-A)") (class "Default")
      (node (ref "D10") (pin "2") (pinfunction "A_2") (pintype "passive"))
      (node (ref "SW10") (pin "1") (pinfunction "1_1") (pintype "passive"))
    )
    (net (code "28") (name "Net-(D11-A)") (class "Default")
      (node (ref "D11") (pin "2") (pinfunction "A_2") (pintype "passive"))
      (node (ref "SW11") (pin "1") (pinfunction "1_1") (pintype "passive"))
    )
    (net (code "29") (name "Net-(D12-A)") (class "Default")
      (node (ref "D12") (pin "2") (pinfunction "A_2") (pintype "passive"))
      (node (ref "SW12") (pin "1") (pinfunction "1_1") (pintype "passive"))
    )
    (net (code "30") (name "Net-(D13-A)") (class "Default")
      (node (ref "D13") (pin "2") (pinfunction "A_2") (pintype "passive"))
      (node (ref "SW13") (pin "1") (pinfunction "1_1") (pintype "passive"))
    )
    (net (code "31") (name "Net-(D14-A)") (class "Default")
      (node (ref "D14") (pin "2") (pinfunction "A_2") (pintype "passive"))
      (node (ref "SW14") (pin "1") (pinfunction "1_1") (pintype "passive"))
    )
    (net (code "32") (name "Net-(D15-A)") (class "Default")
      (node (ref "D15") (pin "2") (pinfunction "A_2") (pintype "passive"))
      (node (ref "SW15") (pin "1") (pinfunction "1_1") (pintype "passive"))
    )
    (net (code "33") (name "Net-(D16-A)") (class "Default")
      (node (ref "D16") (pin "2") (pinfunction "A_2") (pintype "passive"))
      (node (ref "SW16") (pin "1") (pinfunction "1_1") (pintype "passive"))
    )
    (net (code "34") (name "Net-(D17-A)") (class "Default")
      (node (ref "D17") (pin "2") (pinfunction "A_2") (pintype "passive"))
      (node (ref "SW17") (pin "1") (pinfunction "1_1") (pintype "passive"))
    )
    (net (code "35") (name "Net-(D18-A)") (class "Default")
      (node (ref "D18") (pin "2") (pinfunction "A_2") (pintype "passive"))
      (node (ref "SW18") (pin "1") (pinfunction "1_1") (pintype "passive"))
    )
    (net (code "36") (name "Net-(D19-A)") (class "Default")
      (node (ref "D19") (pin "2") (pinfunction "A_2") (pintype "passive"))
      (node (ref "SW19") (pin "1") (pinfunction "1_1") (pintype "passive"))
    )
    (net (code "37") (name "Net-(D20-A)") (class "Default")
      (node (ref "D20") (pin "2") (pinfunction "A_2") (pintype "passive"))
      (node (ref "SW20") (pin "1") (pinfunction "1_1") (pintype "passive"))
    )
    (net (code "38") (name "Net-(D21-C)") (class "Default")
      (node (ref "C1") (pin "1") (pinfunction "1_1") (pintype "passive"))
      (node (ref "D21") (pin "1") (pinfunction "C_1") (pintype "passive"))
      (node (ref "LED1") (pin "1-VDD") (pinfunction "VDD_1-VDD") (pintype "power_in"))
    )
    (net (code "39") (name "Net-(J1-Pad2)") (class "Default")
      (node (ref "J1") (pin "2") (pinfunction "2_2") (pintype "passive"))
      (node (ref "R2") (pin "1") (pinfunction "1_1") (pintype "passive"))
    )
    (net (code "40") (name "Net-(J1-Pad3)") (class "Default")
      (node (ref "J1") (pin "3") (pinfunction "3_3") (pintype "passive"))
      (node (ref "R1") (pin "1") (pinfunction "1_1") (pintype "passive"))
    )
    (net (code "41") (name "Net-(J2-Pad2)") (class "Default")
      (node (ref "J2") (pin "2") (pinfunction "2_2") (pintype "passive"))
      (node (ref "R3") (pin "1") (pinfunction "1_1") (pintype "passive"))
    )
    (net (code "42") (name "Net-(J2-Pad3)") (class "Default")
      (node (ref "J2") (pin "3") (pinfunction "3_3") (pintype "passive"))
      (node (ref "R4") (pin "1") (pinfunction "1_1") (pintype "passive"))
    )
    (net (code "43") (name "Net-(LED1-DO)") (class "Default")
      (node (ref "LED1") (pin "2-DOUT") (pinfunction "DO_2-DOUT") (pintype "output"))
      (node (ref "LED2") (pin "4-DIN") (pinfunction "DI_4-DIN") (pintype "input"))
    )
    (net (code "44") (name "Net-(LED2-DO)") (class "Default")
      (node (ref "LED2") (pin "2-DOUT") (pinfunction "DO_2-DOUT") (pintype "output"))
      (node (ref "LED3") (pin "4-DIN") (pinfunction "DI_4-DIN") (pintype "input"))
    )
    (net (code "45") (name "Net-(LED3-DO)") (class "Default")
      (node (ref "LED3") (pin "2-DOUT") (pinfunction "DO_2-DOUT") (pintype "output"))
      (node (ref "LED4") (pin "4-DIN") (pinfunction "DI_4-DIN") (pintype "input"))
    )
    (net (code "46") (name "Net-(LED4-DO)") (class "Default")
      (node (ref "LED4") (pin "2-DOUT") (pinfunction "DO_2-DOUT") (pintype "output"))
      (node (ref "LED5") (pin "4-DIN") (pinfunction "DI_4-DIN") (pintype "input"))
    )
    (net (code "47") (name "Net-(LED5-DO)") (class "Default")
      (node (ref "LED5") (pin "2-DOUT") (pinfunction "DO_2-DOUT") (pintype "output"))
      (node (ref "LED6") (pin "4-DIN") (pinfunction "DI_4-DIN") (pintype "input"))
    )
    (net (code "48") (name "Net-(LED6-DO)") (class "Default")
      (node (ref "LED6") (pin "2-DOUT") (pinfunction "DO_2-DOUT") (pintype "output"))
      (node (ref "LED7") (pin "4-DIN") (pinfunction "DI_4-DIN") (pintype "input"))
    )
    (net (code "49") (name "Net-(LED7-DO)") (class "Default")
      (node (ref "LED7") (pin "2-DOUT") (pinfunction "DO_2-DOUT") (pintype "output"))
      (node (ref "LED8") (pin "4-DIN") (pinfunction "DI_4-DIN") (pintype "input"))
    )
    (net (code "50") (name "Net-(LED8-DO)") (class "Default")
      (node (ref "LED8") (pin "2-DOUT") (pinfunction "DO_2-DOUT") (pintype "output"))
      (node (ref "LED9") (pin "4-DIN") (pinfunction "DI_4-DIN") (pintype "input"))
    )
    (net (code "51") (name "Net-(LED10-DI)") (class "Default")
      (node (ref "LED10") (pin "4-DIN") (pinfunction "DI_4-DIN") (pintype "input"))
      (node (ref "LED9") (pin "2-DOUT") (pinfunction "DO_2-DOUT") (pintype "output"))
    )
    (net (code "52") (name "Net-(LED10-DO)") (class "Default")
      (node (ref "LED10") (pin "2-DOUT") (pinfunction "DO_2-DOUT") (pintype "output"))
      (node (ref "LED11") (pin "4-DIN") (pinfunction "DI_4-DIN") (pintype "input"))
    )
    (net (code "53") (name "Net-(LED11-DO)") (class "Default")
      (node (ref "LED11") (pin "2-DOUT") (pinfunction "DO_2-DOUT") (pintype "output"))
      (node (ref "LED12") (pin "4-DIN") (pinfunction "DI_4-DIN") (pintype "input"))
    )
    (net (code "54") (name "Net-(LED12-DO)") (class "Default")
      (node (ref "LED12") (pin "2-DOUT") (pinfunction "DO_2-DOUT") (pintype "output"))
      (node (ref "LED13") (pin "4-DIN") (pinfunction "DI_4-DIN") (pintype "input"))
    )
    (net (code "55") (name "Net-(LED13-DO)") (class "Default")
      (node (ref "LED13") (pin "2-DOUT") (pinfunction "DO_2-DOUT") (pintype "output"))
      (node (ref "LED14") (pin "4-DIN") (pinfunction "DI_4-DIN") (pintype "input"))
    )
    (net (code "56") (name "Net-(LED14-DO)") (class "Default")
      (node (ref "LED14") (pin "2-DOUT") (pinfunction "DO_2-DOUT") (pintype "output"))
      (node (ref "LED15") (pin "4-DIN") (pinfunction "DI_4-DIN") (pintype "input"))
    )
    (net (code "57") (name "Net-(LED15-DO)") (class "Default")
      (node (ref "LED15") (pin "2-DOUT") (pinfunction "DO_2-DOUT") (pintype "output"))
      (node (ref "LED16") (pin "4-DIN") (pinfunction "DI_4-DIN") (pintype "input"))
    )
    (net (code "58") (name "Net-(LED16-DO)") (class "Default")
      (node (ref "LED16") (pin "2-DOUT") (pinfunction "DO_2-DOUT") (pintype "output"))
      (node (ref "LED17") (pin "4-DIN") (pinfunction "DI_4-DIN") (pintype "input"))
    )
    (net (code "59") (name "Net-(LED17-DO)") (class "Default")
      (node (ref "LED17") (pin "2-DOUT") (pinfunction "DO_2-DOUT") (pintype "output"))
      (node (ref "LED18") (pin "4-DIN") (pinfunction "DI_4-DIN") (pintype "input"))
    )
    (net (code "60") (name "Net-(LED18-DO)") (class "Default")
      (node (ref "LED18") (pin "2-DOUT") (pinfunction "DO_2-DOUT") (pintype "output"))
      (node (ref "LED19") (pin "4-DIN") (pinfunction "DI_4-DIN") (pintype "input"))
    )
    (net (code "61") (name "Net-(LED19-DO)") (class "Default")
      (node (ref "LED19") (pin "2-DOUT") (pinfunction "DO_2-DOUT") (pintype "output"))
      (node (ref "LED20") (pin "4-DIN") (pinfunction "DI_4-DIN") (pintype "input"))
    )
    (net (code "62") (name "unconnected-(LED20-DO-Pad2-DOUT)") (class "Default")
      (node (ref "LED20") (pin "2-DOUT") (pinfunction "DO_2-DOUT") (pintype "output"))
    )
    (net (code "63") (name "unconnected-(U1-11(MOSI)-Pad14)") (class "Default")
      (node (ref "U1") (pin "14") (pinfunction "11(MOSI)_14") (pintype "bidirectional"))
    )
    (net (code "64") (name "unconnected-(U1-13(SCK)-Pad16)") (class "Default")
      (node (ref "U1") (pin "16") (pinfunction "13(SCK)_16") (pintype "bidirectional"))
    )
    (net (code "65") (name "unconnected-(U1-A0-Pad17)") (class "Default")
      (node (ref "U1") (pin "17") (pinfunction "A0_17") (pintype "bidirectional"))
    )
    (net (code "66") (name "unconnected-(U1-A1-Pad18)") (class "Default")
      (node (ref "U1") (pin "18") (pinfunction "A1_18") (pintype "bidirectional"))
    )
    (net (code "67") (name "unconnected-(U1-A2-Pad19)") (class "Default")
      (node (ref "U1") (pin "19") (pinfunction "A2_19") (pintype "bidirectional"))
    )
    (net (code "68") (name "unconnected-(U1-A3-Pad20)") (class "Default")
      (node (ref "U1") (pin "20") (pinfunction "A3_20") (pintype "bidirectional"))
    )
    (net (code "69") (name "unconnected-(U1-RESET-Pad22)") (class "Default")
      (node (ref "U1") (pin "22") (pinfunction "RESET_22") (pintype "bidirectional"))
    )
  )
)
